# ArdSensor.net
KiCad netlist of a schematic drawn in EAGLE
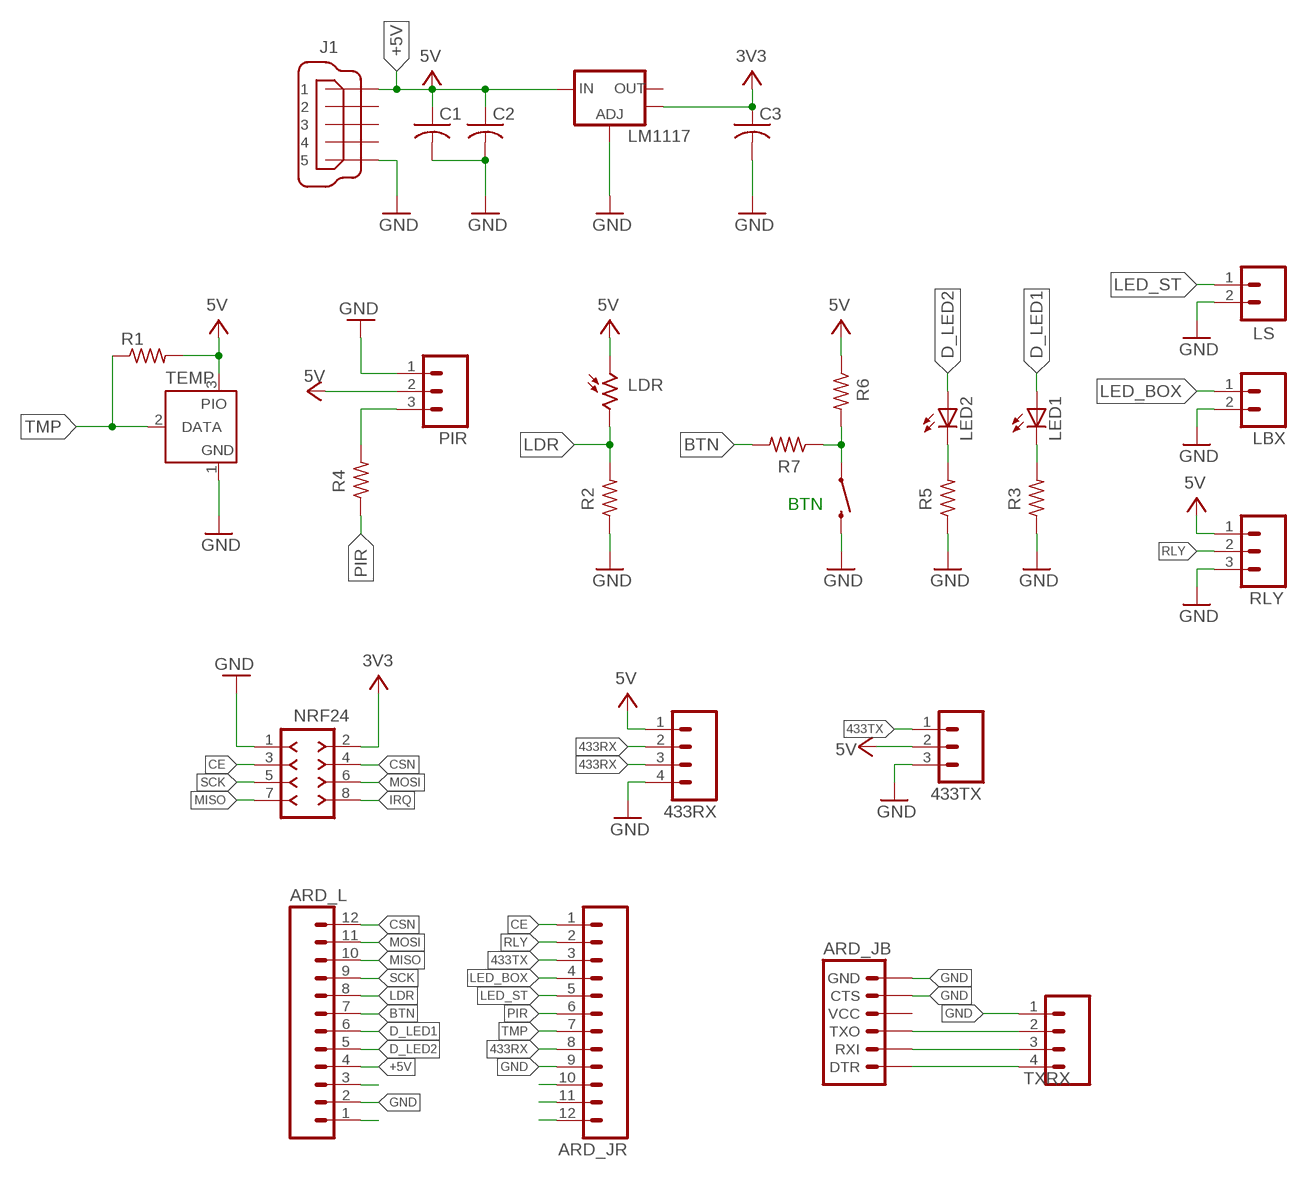
[diagram p0: schematic, sheet 1]

(export (version "E")
  (design (tool "Eeschema 10.0.6"))
  (components
    (comp (ref "433RX")
      (value "M04PTH")
      (footprint "eagle-import:1X04")
      (libsource (lib "eagle-import") (part "M04PTH"))
    )
    (comp (ref "433TX")
      (value "M03PTH")
      (footprint "eagle-import:1X03")
      (libsource (lib "eagle-import") (part "M03PTH"))
    )
    (comp (ref "ARD_JB")
      (value "ARDUINO_SERIAL_PROGRAMPTH")
      (footprint "eagle-import:1X06")
      (libsource (lib "eagle-import") (part "ARDUINO_SERIAL_PROGRAMPTH"))
    )
    (comp (ref "ARD_JR")
      (value "M12PTH")
      (footprint "eagle-import:1X12")
      (libsource (lib "eagle-import") (part "M12PTH"))
    )
    (comp (ref "ARD_L")
      (value "M12PTH")
      (footprint "eagle-import:1X12")
      (libsource (lib "eagle-import") (part "M12PTH"))
    )
    (comp (ref "BTN")
      (value "SWITCH-MOMENTARY-2SMD-1101NE")
      (footprint "eagle-import:TACTILE-SWITCH-1101NE")
      (libsource (lib "eagle-import") (part "SWITCH-MOMENTARY-2SMD-1101NE"))
    )
    (comp (ref "C1")
      (value "C-USC0805")
      (footprint "eagle-import:C0805")
      (libsource (lib "eagle-import") (part "C-USC0805"))
    )
    (comp (ref "C2")
      (value "C-USC0805")
      (footprint "eagle-import:C0805")
      (libsource (lib "eagle-import") (part "C-USC0805"))
    )
    (comp (ref "C3")
      (value "C-USC0805")
      (footprint "eagle-import:C0805")
      (libsource (lib "eagle-import") (part "C-USC0805"))
    )
    (comp (ref "J1")
      (value "MICRO-USB-ZX62R-B-5P")
      (footprint "eagle-import:ZX62R-B-5P")
      (libsource (lib "eagle-import") (part "MICRO-USB-ZX62R-B-5P"))
    )
    (comp (ref "LBX")
      (value "M02PTH")
      (footprint "eagle-import:1X02")
      (libsource (lib "eagle-import") (part "M02PTH"))
    )
    (comp (ref "LDR")
      (value "D11")
      (footprint "eagle-import:BPX65")
      (libsource (lib "eagle-import") (part "D11"))
    )
    (comp (ref "LED1")
      (value "LEDCHIPLED_0805")
      (footprint "eagle-import:CHIPLED_0805")
      (libsource (lib "eagle-import") (part "LEDCHIPLED_0805"))
    )
    (comp (ref "LED2")
      (value "LEDCHIPLED_0805")
      (footprint "eagle-import:CHIPLED_0805")
      (libsource (lib "eagle-import") (part "LEDCHIPLED_0805"))
    )
    (comp (ref "LM1117")
      (value "V_REG_LM1117SOT223")
      (footprint "eagle-import:SOT223")
      (libsource (lib "eagle-import") (part "V_REG_LM1117SOT223"))
    )
    (comp (ref "LS")
      (value "M02PTH")
      (footprint "eagle-import:1X02")
      (libsource (lib "eagle-import") (part "M02PTH"))
    )
    (comp (ref "NRF24")
      (value "F-2X04-DIL-100")
      (footprint "eagle-import:DIL-100-2X04")
      (libsource (lib "eagle-import") (part "F-2X04-DIL-100"))
    )
    (comp (ref "PIR")
      (value "M03PTH")
      (footprint "eagle-import:1X03")
      (libsource (lib "eagle-import") (part "M03PTH"))
    )
    (comp (ref "R1")
      (value "R-US_R0805")
      (footprint "eagle-import:R0805")
      (libsource (lib "eagle-import") (part "R-US_R0805"))
    )
    (comp (ref "R2")
      (value "R-US_R0805")
      (footprint "eagle-import:R0805")
      (libsource (lib "eagle-import") (part "R-US_R0805"))
    )
    (comp (ref "R3")
      (value "R-US_R0805")
      (footprint "eagle-import:R0805")
      (libsource (lib "eagle-import") (part "R-US_R0805"))
    )
    (comp (ref "R4")
      (value "R-US_R0805")
      (footprint "eagle-import:R0805")
      (libsource (lib "eagle-import") (part "R-US_R0805"))
    )
    (comp (ref "R5")
      (value "R-US_R0805")
      (footprint "eagle-import:R0805")
      (libsource (lib "eagle-import") (part "R-US_R0805"))
    )
    (comp (ref "R6")
      (value "R-US_R0805")
      (footprint "eagle-import:R0805")
      (libsource (lib "eagle-import") (part "R-US_R0805"))
    )
    (comp (ref "R7")
      (value "R-US_R0805")
      (footprint "eagle-import:R0805")
      (libsource (lib "eagle-import") (part "R-US_R0805"))
    )
    (comp (ref "RLY")
      (value "M03PTH")
      (footprint "eagle-import:1X03")
      (libsource (lib "eagle-import") (part "M03PTH"))
    )
    (comp (ref "TEMP")
      (value "DS2405")
      (footprint "eagle-import:TO92-")
      (fields (field (name "MF") "DALLAS SEMICONDUCTOR"))
      (libsource (lib "eagle-import") (part "DS2405"))
    )
    (comp (ref "TXRX")
      (value "M04PTH")
      (footprint "eagle-import:1X04")
      (libsource (lib "eagle-import") (part "M04PTH"))
    )
  )
  (nets
    (net (code "1") (name "+5V") (class "Default")
      (node (ref "433RX") (pin "1") (pinfunction "1_1") (pintype "passive"))
      (node (ref "433TX") (pin "2") (pinfunction "2_2") (pintype "passive"))
      (node (ref "ARD_L") (pin "4") (pinfunction "4_4") (pintype "passive"))
      (node (ref "C1") (pin "1") (pinfunction "1_1") (pintype "passive"))
      (node (ref "C2") (pin "1") (pinfunction "1_1") (pintype "passive"))
      (node (ref "J1") (pin "1") (pinfunction "1_1") (pintype "input"))
      (node (ref "LDR") (pin "A") (pinfunction "1_A") (pintype "passive"))
      (node (ref "LM1117") (pin "3") (pinfunction "IN_3") (pintype "input"))
      (node (ref "PIR") (pin "2") (pinfunction "2_2") (pintype "passive"))
      (node (ref "R1") (pin "2") (pinfunction "2_2") (pintype "passive"))
      (node (ref "R6") (pin "1") (pinfunction "1_1") (pintype "passive"))
      (node (ref "RLY") (pin "1") (pinfunction "1_1") (pintype "passive"))
      (node (ref "TEMP") (pin "3") (pinfunction "PIO_3") (pintype "passive"))
    )
    (net (code "2") (name "3V3") (class "Default")
      (node (ref "C3") (pin "1") (pinfunction "1_1") (pintype "passive"))
      (node (ref "LM1117") (pin "4") (pinfunction "OUT_4") (pintype "output"))
      (node (ref "NRF24") (pin "2") (pinfunction "2_2") (pintype "passive"))
    )
    (net (code "3") (name "433RX") (class "Default")
      (node (ref "433RX") (pin "2") (pinfunction "2_2") (pintype "passive"))
      (node (ref "433RX") (pin "3") (pinfunction "3_3") (pintype "passive"))
      (node (ref "ARD_JR") (pin "8") (pinfunction "8_8") (pintype "passive"))
    )
    (net (code "4") (name "433TX") (class "Default")
      (node (ref "433TX") (pin "1") (pinfunction "1_1") (pintype "passive"))
      (node (ref "ARD_JR") (pin "3") (pinfunction "3_3") (pintype "passive"))
    )
    (net (code "5") (name "BTN") (class "Default")
      (node (ref "ARD_L") (pin "7") (pinfunction "7_7") (pintype "passive"))
      (node (ref "R7") (pin "2") (pinfunction "2_2") (pintype "passive"))
    )
    (net (code "6") (name "CE") (class "Default")
      (node (ref "ARD_JR") (pin "1") (pinfunction "1_1") (pintype "passive"))
      (node (ref "NRF24") (pin "3") (pinfunction "3_3") (pintype "passive"))
    )
    (net (code "7") (name "CSN") (class "Default")
      (node (ref "ARD_L") (pin "12") (pinfunction "12_12") (pintype "passive"))
      (node (ref "NRF24") (pin "4") (pinfunction "4_4") (pintype "passive"))
    )
    (net (code "8") (name "D_LED1") (class "Default")
      (node (ref "ARD_L") (pin "6") (pinfunction "6_6") (pintype "passive"))
      (node (ref "LED1") (pin "A") (pinfunction "A_A") (pintype "passive"))
    )
    (net (code "9") (name "D_LED2") (class "Default")
      (node (ref "ARD_L") (pin "5") (pinfunction "5_5") (pintype "passive"))
      (node (ref "LED2") (pin "A") (pinfunction "A_A") (pintype "passive"))
    )
    (net (code "10") (name "GND") (class "Default")
      (node (ref "433RX") (pin "4") (pinfunction "4_4") (pintype "passive"))
      (node (ref "433TX") (pin "3") (pinfunction "3_3") (pintype "passive"))
      (node (ref "ARD_JB") (pin "5") (pinfunction "CTS_5") (pintype "passive"))
      (node (ref "ARD_JB") (pin "6") (pinfunction "GND_6") (pintype "passive"))
      (node (ref "ARD_JR") (pin "9") (pinfunction "9_9") (pintype "passive"))
      (node (ref "ARD_L") (pin "2") (pinfunction "2_2") (pintype "passive"))
      (node (ref "BTN") (pin "2") (pinfunction "2_2") (pintype "passive"))
      (node (ref "C1") (pin "2") (pinfunction "2_2") (pintype "passive"))
      (node (ref "C2") (pin "2") (pinfunction "2_2") (pintype "passive"))
      (node (ref "C3") (pin "2") (pinfunction "2_2") (pintype "passive"))
      (node (ref "J1") (pin "5") (pinfunction "5_5") (pintype "input"))
      (node (ref "LBX") (pin "2") (pinfunction "2_2") (pintype "passive"))
      (node (ref "LM1117") (pin "1") (pinfunction "ADJ_1") (pintype "input"))
      (node (ref "LS") (pin "2") (pinfunction "2_2") (pintype "passive"))
      (node (ref "NRF24") (pin "1") (pinfunction "1_1") (pintype "passive"))
      (node (ref "PIR") (pin "1") (pinfunction "1_1") (pintype "passive"))
      (node (ref "R2") (pin "1") (pinfunction "1_1") (pintype "passive"))
      (node (ref "R3") (pin "1") (pinfunction "1_1") (pintype "passive"))
      (node (ref "R5") (pin "1") (pinfunction "1_1") (pintype "passive"))
      (node (ref "RLY") (pin "3") (pinfunction "3_3") (pintype "passive"))
      (node (ref "TEMP") (pin "1") (pinfunction "GND_1") (pintype "passive"))
      (node (ref "TXRX") (pin "1") (pinfunction "1_1") (pintype "passive"))
    )
    (net (code "11") (name "IRQ") (class "Default")
      (node (ref "NRF24") (pin "8") (pinfunction "8_8") (pintype "passive"))
    )
    (net (code "12") (name "LDR") (class "Default")
      (node (ref "ARD_L") (pin "8") (pinfunction "8_8") (pintype "passive"))
      (node (ref "LDR") (pin "K") (pinfunction "2_K") (pintype "passive"))
      (node (ref "R2") (pin "2") (pinfunction "2_2") (pintype "passive"))
    )
    (net (code "13") (name "LED_BOX") (class "Default")
      (node (ref "ARD_JR") (pin "4") (pinfunction "4_4") (pintype "passive"))
      (node (ref "LBX") (pin "1") (pinfunction "1_1") (pintype "passive"))
    )
    (net (code "14") (name "LED_ST") (class "Default")
      (node (ref "ARD_JR") (pin "5") (pinfunction "5_5") (pintype "passive"))
      (node (ref "LS") (pin "1") (pinfunction "1_1") (pintype "passive"))
    )
    (net (code "15") (name "MISO") (class "Default")
      (node (ref "ARD_L") (pin "10") (pinfunction "10_10") (pintype "passive"))
      (node (ref "NRF24") (pin "7") (pinfunction "7_7") (pintype "passive"))
    )
    (net (code "16") (name "MOSI") (class "Default")
      (node (ref "ARD_L") (pin "11") (pinfunction "11_11") (pintype "passive"))
      (node (ref "NRF24") (pin "6") (pinfunction "6_6") (pintype "passive"))
    )
    (net (code "17") (name "Net-(ARD_JB-DTR)") (class "Default")
      (node (ref "ARD_JB") (pin "1") (pinfunction "DTR_1") (pintype "passive"))
      (node (ref "TXRX") (pin "4") (pinfunction "4_4") (pintype "passive"))
    )
    (net (code "18") (name "Net-(ARD_JB-RXI)") (class "Default")
      (node (ref "ARD_JB") (pin "2") (pinfunction "RXI_2") (pintype "passive"))
      (node (ref "TXRX") (pin "3") (pinfunction "3_3") (pintype "passive"))
    )
    (net (code "19") (name "Net-(ARD_JB-TXO)") (class "Default")
      (node (ref "ARD_JB") (pin "3") (pinfunction "TXO_3") (pintype "passive"))
      (node (ref "TXRX") (pin "2") (pinfunction "2_2") (pintype "passive"))
    )
    (net (code "20") (name "Net-(BTN-Pad1)") (class "Default")
      (node (ref "BTN") (pin "1") (pinfunction "1_1") (pintype "passive"))
      (node (ref "R6") (pin "2") (pinfunction "2_2") (pintype "passive"))
      (node (ref "R7") (pin "1") (pinfunction "1_1") (pintype "passive"))
    )
    (net (code "21") (name "Net-(LED1-PadC)") (class "Default")
      (node (ref "LED1") (pin "C") (pinfunction "C_C") (pintype "passive"))
      (node (ref "R3") (pin "2") (pinfunction "2_2") (pintype "passive"))
    )
    (net (code "22") (name "Net-(LED2-PadC)") (class "Default")
      (node (ref "LED2") (pin "C") (pinfunction "C_C") (pintype "passive"))
      (node (ref "R5") (pin "2") (pinfunction "2_2") (pintype "passive"))
    )
    (net (code "23") (name "Net-(PIR-Pad3)") (class "Default")
      (node (ref "PIR") (pin "3") (pinfunction "3_3") (pintype "passive"))
      (node (ref "R4") (pin "2") (pinfunction "2_2") (pintype "passive"))
    )
    (net (code "24") (name "PIR") (class "Default")
      (node (ref "ARD_JR") (pin "6") (pinfunction "6_6") (pintype "passive"))
      (node (ref "R4") (pin "1") (pinfunction "1_1") (pintype "passive"))
    )
    (net (code "25") (name "RLY") (class "Default")
      (node (ref "ARD_JR") (pin "2") (pinfunction "2_2") (pintype "passive"))
      (node (ref "RLY") (pin "2") (pinfunction "2_2") (pintype "passive"))
    )
    (net (code "26") (name "SCK") (class "Default")
      (node (ref "ARD_L") (pin "9") (pinfunction "9_9") (pintype "passive"))
      (node (ref "NRF24") (pin "5") (pinfunction "5_5") (pintype "passive"))
    )
    (net (code "27") (name "TMP") (class "Default")
      (node (ref "ARD_JR") (pin "7") (pinfunction "7_7") (pintype "passive"))
      (node (ref "R1") (pin "1") (pinfunction "1_1") (pintype "passive"))
      (node (ref "TEMP") (pin "2") (pinfunction "DATA_2") (pintype "input"))
    )
    (net (code "28") (name "unconnected-(ARD_JB-VCC-Pad4)") (class "Default")
      (node (ref "ARD_JB") (pin "4") (pinfunction "VCC_4") (pintype "passive"))
    )
    (net (code "29") (name "unconnected-(ARD_JR-Pad10)") (class "Default")
      (node (ref "ARD_JR") (pin "10") (pinfunction "10_10") (pintype "passive"))
    )
    (net (code "30") (name "unconnected-(ARD_JR-Pad11)") (class "Default")
      (node (ref "ARD_JR") (pin "11") (pinfunction "11_11") (pintype "passive"))
    )
    (net (code "31") (name "unconnected-(ARD_JR-Pad12)") (class "Default")
      (node (ref "ARD_JR") (pin "12") (pinfunction "12_12") (pintype "passive"))
    )
    (net (code "32") (name "unconnected-(ARD_L-Pad1)") (class "Default")
      (node (ref "ARD_L") (pin "1") (pinfunction "1_1") (pintype "passive"))
    )
    (net (code "33") (name "unconnected-(ARD_L-Pad3)") (class "Default")
      (node (ref "ARD_L") (pin "3") (pinfunction "3_3") (pintype "passive"))
    )
    (net (code "34") (name "unconnected-(J1-Pad2)") (class "Default")
      (node (ref "J1") (pin "2") (pinfunction "2_2") (pintype "input"))
    )
    (net (code "35") (name "unconnected-(J1-Pad3)") (class "Default")
      (node (ref "J1") (pin "3") (pinfunction "3_3") (pintype "input"))
    )
    (net (code "36") (name "unconnected-(J1-Pad4)") (class "Default")
      (node (ref "J1") (pin "4") (pinfunction "4_4") (pintype "input"))
    )
    (net (code "37") (name "unconnected-(LM1117-OUT-Pad2)") (class "Default")
      (node (ref "LM1117") (pin "2") (pinfunction "OUT_2") (pintype "output"))
    )
  )
)
